# Qwiic_High_Performance_Magnetometer.net
KiCad netlist of a schematic drawn in EAGLE
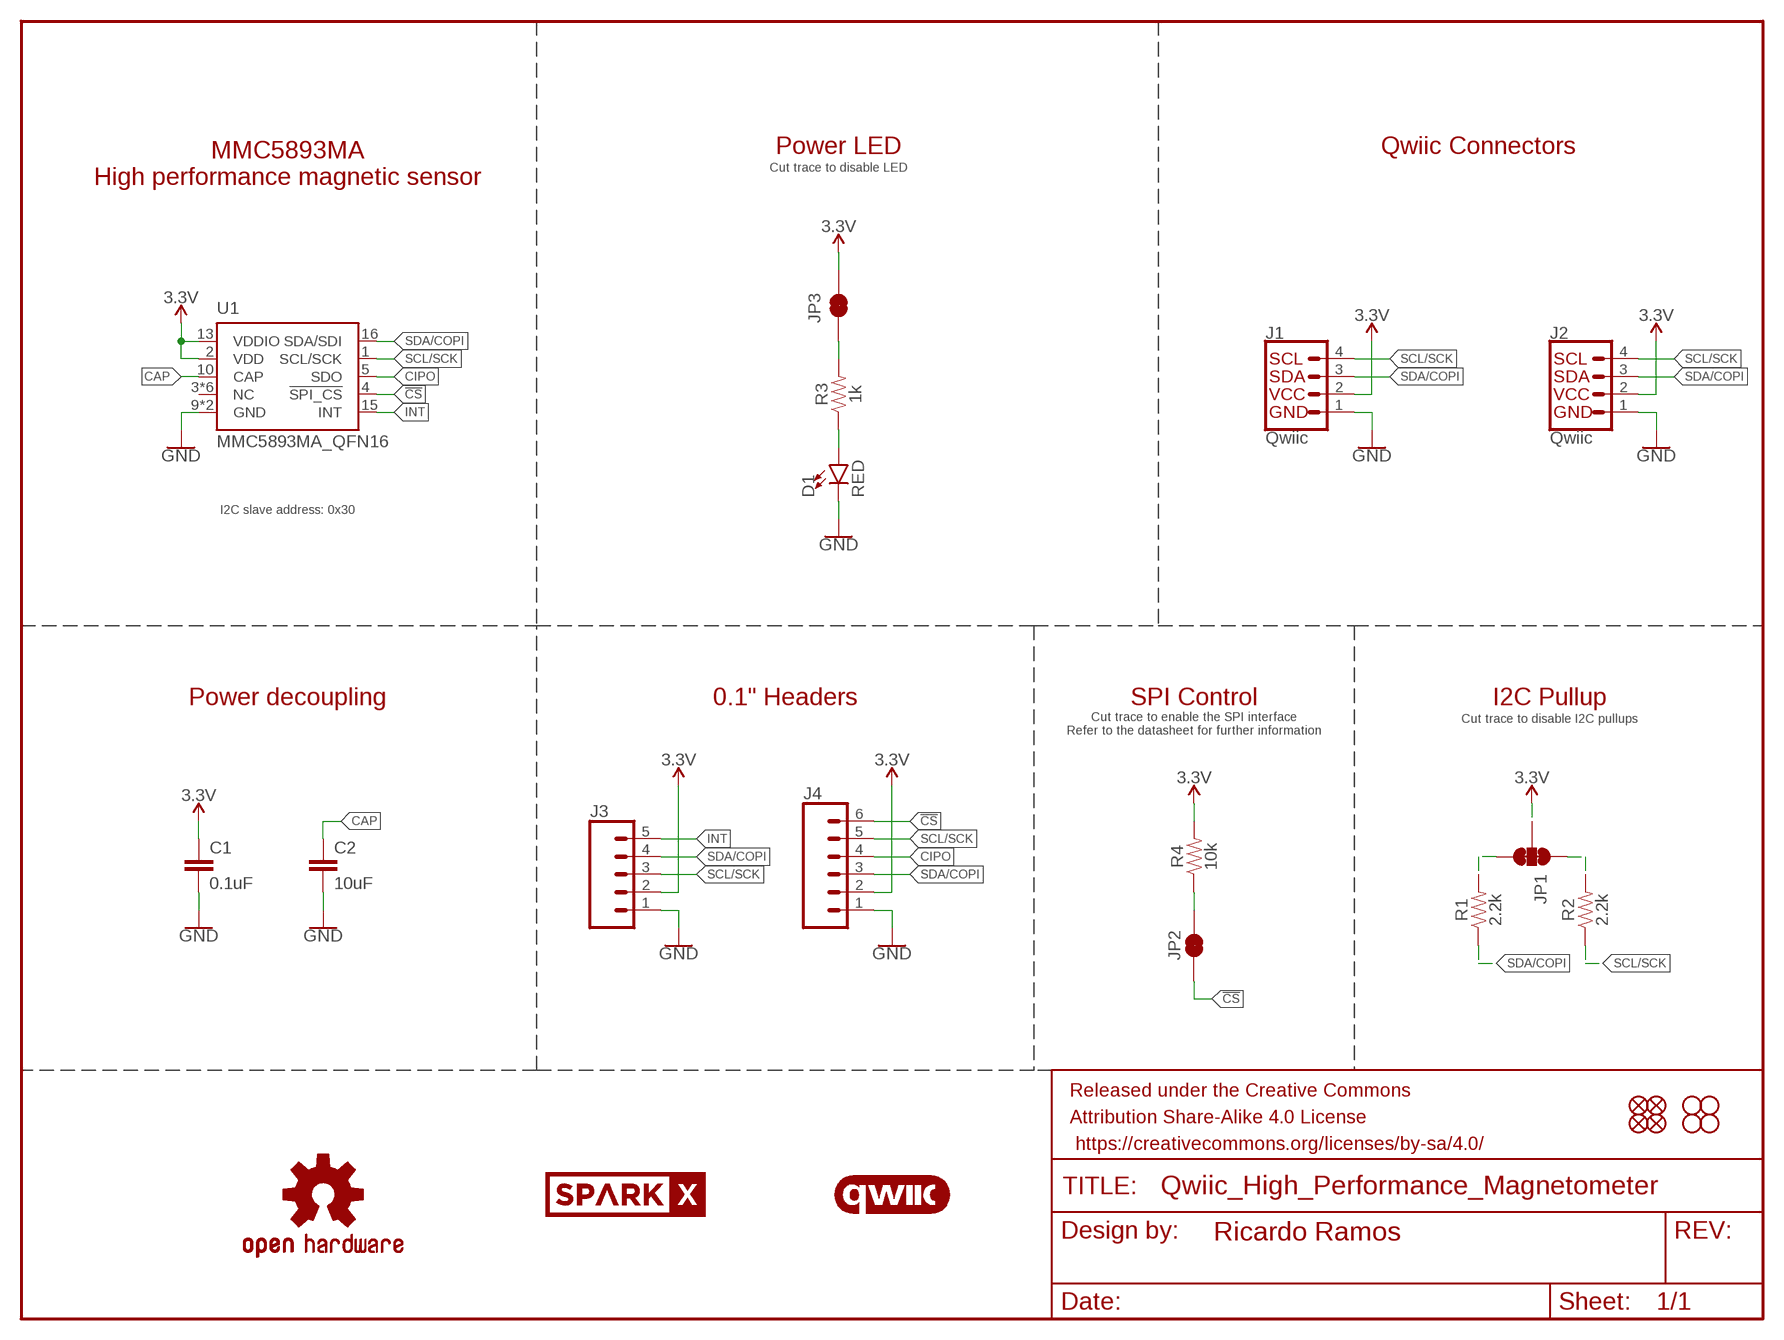
[diagram p0: schematic, sheet 1]

(export (version "E")
  (design (tool "Eeschema 10.0.6"))
  (components
    (comp (ref "C1")
      (value "0.1uF")
      (footprint "eagle-import:0603")
      (libsource (lib "eagle-import") (part "0.1UF-0603-25V-(+80/-20%)"))
    )
    (comp (ref "C2")
      (value "10uF")
      (footprint "eagle-import:0603")
      (libsource (lib "eagle-import") (part "10UF-0603-6.3V-20%"))
    )
    (comp (ref "D1")
      (value "RED")
      (footprint "eagle-import:LED-0603")
      (libsource (lib "eagle-import") (part "LED-RED0603"))
    )
    (comp (ref "FD1")
      (value "FIDUCIAL1X2")
      (footprint "eagle-import:FIDUCIAL-1X2")
      (libsource (lib "eagle-import") (part "FIDUCIAL1X2"))
    )
    (comp (ref "FD2")
      (value "FIDUCIAL1X2")
      (footprint "eagle-import:FIDUCIAL-1X2")
      (libsource (lib "eagle-import") (part "FIDUCIAL1X2"))
    )
    (comp (ref "FD3")
      (value "FIDUCIAL1X2")
      (footprint "eagle-import:FIDUCIAL-1X2")
      (libsource (lib "eagle-import") (part "FIDUCIAL1X2"))
    )
    (comp (ref "FD4")
      (value "FIDUCIAL1X2")
      (footprint "eagle-import:FIDUCIAL-1X2")
      (libsource (lib "eagle-import") (part "FIDUCIAL1X2"))
    )
    (comp (ref "FRAME1")
      (value "FRAME-LETTERNO_PACKAGE")
      (footprint "eagle-import:DUMMY")
      (fields (field (name "DESIGNER") "Nobody") (field (name "DESIGNER_1") "Ricardo Ramos"))
      (libsource (lib "eagle-import") (part "FRAME-LETTERNO_PACKAGE"))
    )
    (comp (ref "H1")
      (value "STAND-OFF")
      (footprint "eagle-import:STAND-OFF")
      (libsource (lib "eagle-import") (part "STAND-OFF"))
    )
    (comp (ref "H2")
      (value "STAND-OFF")
      (footprint "eagle-import:STAND-OFF")
      (libsource (lib "eagle-import") (part "STAND-OFF"))
    )
    (comp (ref "H3")
      (value "STAND-OFF")
      (footprint "eagle-import:STAND-OFF")
      (libsource (lib "eagle-import") (part "STAND-OFF"))
    )
    (comp (ref "H4")
      (value "STAND-OFF")
      (footprint "eagle-import:STAND-OFF")
      (libsource (lib "eagle-import") (part "STAND-OFF"))
    )
    (comp (ref "J1")
      (value "Qwiic")
      (footprint "eagle-import:JST04_1MM_RA")
      (libsource (lib "eagle-import") (part "QWIIC_CONNECTORJS-1MM"))
    )
    (comp (ref "J2")
      (value "Qwiic")
      (footprint "eagle-import:JST04_1MM_RA")
      (libsource (lib "eagle-import") (part "QWIIC_CONNECTORJS-1MM"))
    )
    (comp (ref "J3")
      (value "CONN_05NO_SILK")
      (footprint "eagle-import:1X05_NO_SILK")
      (libsource (lib "eagle-import") (part "CONN_05NO_SILK"))
    )
    (comp (ref "J4")
      (value "CONN_06NO_SILK_NO_POP")
      (footprint "eagle-import:1X06_NO_SILK")
      (libsource (lib "eagle-import") (part "CONN_06NO_SILK_NO_POP"))
    )
    (comp (ref "JP1")
      (value "JUMPER-SMT_3_2-NC_TRACE_SILK")
      (footprint "eagle-import:SMT-JUMPER_3_2-NC_TRACE_SILK")
      (libsource (lib "eagle-import") (part "JUMPER-SMT_3_2-NC_TRACE_SILK"))
    )
    (comp (ref "JP2")
      (value "JUMPER-SMT_2_NC_TRACE_SILK")
      (footprint "eagle-import:SMT-JUMPER_2_NC_TRACE_SILK")
      (libsource (lib "eagle-import") (part "JUMPER-SMT_2_NC_TRACE_SILK"))
    )
    (comp (ref "JP3")
      (value "JUMPER-SMT_2_NC_TRACE_SILK")
      (footprint "eagle-import:SMT-JUMPER_2_NC_TRACE_SILK")
      (libsource (lib "eagle-import") (part "JUMPER-SMT_2_NC_TRACE_SILK"))
    )
    (comp (ref "LOGO1")
      (value "OSHW-LOGOMINI")
      (footprint "eagle-import:OSHW-LOGO-MINI")
      (libsource (lib "eagle-import") (part "OSHW-LOGOMINI"))
    )
    (comp (ref "LOGO2")
      (value "QWIIC_LOGO_5MM")
      (footprint "eagle-import:QWIIC_5MM")
      (libsource (lib "eagle-import") (part "QWIIC_LOGO_5MM"))
    )
    (comp (ref "R1")
      (value "2.2k")
      (footprint "eagle-import:0603")
      (libsource (lib "eagle-import") (part "2.2KOHM-0603-1/10W-1%"))
    )
    (comp (ref "R2")
      (value "2.2k")
      (footprint "eagle-import:0603")
      (libsource (lib "eagle-import") (part "2.2KOHM-0603-1/10W-1%"))
    )
    (comp (ref "R3")
      (value "1k")
      (footprint "eagle-import:0603")
      (libsource (lib "eagle-import") (part "1KOHM-0603-1/10W-1%"))
    )
    (comp (ref "R4")
      (value "10k")
      (footprint "eagle-import:0603")
      (libsource (lib "eagle-import") (part "10KOHM-0603-1/10W-1%"))
    )
    (comp (ref "U$36")
      (value "SPARKX-LOGO2")
      (footprint "eagle-import:SPARKX-TINY")
      (libsource (lib "eagle-import") (part "SPARKX-LOGO2"))
    )
    (comp (ref "U$37")
      (value "SPARKX-LOGO3")
      (footprint "eagle-import:SPARKX-SMALL")
      (libsource (lib "eagle-import") (part "SPARKX-LOGO3"))
    )
    (comp (ref "U1")
      (value "MMC5893MA_QFN16")
      (footprint "eagle-import:LGA-16-3X3MM-4X4PINS")
      (libsource (lib "eagle-import") (part "MMC5893MA_QFN16"))
    )
  )
  (nets
    (net (code "1") (name "/~{CS}") (class "Default")
      (node (ref "J4") (pin "6") (pinfunction "6_6") (pintype "passive"))
      (node (ref "JP2") (pin "1") (pinfunction "1_1") (pintype "passive"))
      (node (ref "U1") (pin "4") (pinfunction "~{SPI_CS}_4") (pintype "input"))
    )
    (net (code "2") (name "3.3V") (class "Default")
      (node (ref "C1") (pin "1") (pinfunction "1_1") (pintype "passive"))
      (node (ref "J1") (pin "2") (pinfunction "2_2") (pintype "power_in"))
      (node (ref "J2") (pin "2") (pinfunction "2_2") (pintype "power_in"))
      (node (ref "J3") (pin "2") (pinfunction "2_2") (pintype "passive"))
      (node (ref "J4") (pin "2") (pinfunction "2_2") (pintype "passive"))
      (node (ref "JP1") (pin "2") (pinfunction "2_2") (pintype "passive"))
      (node (ref "JP3") (pin "2") (pinfunction "2_2") (pintype "passive"))
      (node (ref "R4") (pin "2") (pinfunction "2_2") (pintype "passive"))
      (node (ref "U1") (pin "13") (pinfunction "VDDIO_13") (pintype "power_in"))
      (node (ref "U1") (pin "2") (pinfunction "VDD_2") (pintype "power_in"))
    )
    (net (code "3") (name "CAP") (class "Default")
      (node (ref "C2") (pin "1") (pinfunction "1_1") (pintype "passive"))
      (node (ref "U1") (pin "10") (pinfunction "CAP_10") (pintype "passive"))
    )
    (net (code "4") (name "CIPO") (class "Default")
      (node (ref "J4") (pin "4") (pinfunction "4_4") (pintype "passive"))
      (node (ref "U1") (pin "5") (pinfunction "SDO_5") (pintype "output"))
    )
    (net (code "5") (name "GND") (class "Default")
      (node (ref "C1") (pin "2") (pinfunction "2_2") (pintype "passive"))
      (node (ref "C2") (pin "2") (pinfunction "2_2") (pintype "passive"))
      (node (ref "D1") (pin "C") (pinfunction "C_C") (pintype "passive"))
      (node (ref "J1") (pin "1") (pinfunction "1_1") (pintype "power_in"))
      (node (ref "J2") (pin "1") (pinfunction "1_1") (pintype "power_in"))
      (node (ref "J3") (pin "1") (pinfunction "1_1") (pintype "passive"))
      (node (ref "J4") (pin "1") (pinfunction "1_1") (pintype "passive"))
      (node (ref "U1") (pin "11") (pinfunction "GND_11") (pintype "power_in"))
      (node (ref "U1") (pin "9") (pinfunction "GND_9") (pintype "power_in"))
    )
    (net (code "6") (name "INT") (class "Default")
      (node (ref "J3") (pin "5") (pinfunction "5_5") (pintype "passive"))
      (node (ref "U1") (pin "15") (pinfunction "INT_15") (pintype "output"))
    )
    (net (code "7") (name "Net-(D1-PadA)") (class "Default")
      (node (ref "D1") (pin "A") (pinfunction "A_A") (pintype "passive"))
      (node (ref "R3") (pin "1") (pinfunction "1_1") (pintype "passive"))
    )
    (net (code "8") (name "Net-(JP1-Pad1)") (class "Default")
      (node (ref "JP1") (pin "1") (pinfunction "1_1") (pintype "passive"))
      (node (ref "R2") (pin "2") (pinfunction "2_2") (pintype "passive"))
    )
    (net (code "9") (name "Net-(JP1-Pad3)") (class "Default")
      (node (ref "JP1") (pin "3") (pinfunction "3_3") (pintype "passive"))
      (node (ref "R1") (pin "2") (pinfunction "2_2") (pintype "passive"))
    )
    (net (code "10") (name "Net-(JP2-Pad2)") (class "Default")
      (node (ref "JP2") (pin "2") (pinfunction "2_2") (pintype "passive"))
      (node (ref "R4") (pin "1") (pinfunction "1_1") (pintype "passive"))
    )
    (net (code "11") (name "Net-(JP3-Pad1)") (class "Default")
      (node (ref "JP3") (pin "1") (pinfunction "1_1") (pintype "passive"))
      (node (ref "R3") (pin "2") (pinfunction "2_2") (pintype "passive"))
    )
    (net (code "12") (name "SCL{slash}SCK") (class "Default")
      (node (ref "J1") (pin "4") (pinfunction "4_4") (pintype "passive"))
      (node (ref "J2") (pin "4") (pinfunction "4_4") (pintype "passive"))
      (node (ref "J3") (pin "3") (pinfunction "3_3") (pintype "passive"))
      (node (ref "J4") (pin "5") (pinfunction "5_5") (pintype "passive"))
      (node (ref "R2") (pin "1") (pinfunction "1_1") (pintype "passive"))
      (node (ref "U1") (pin "1") (pinfunction "SCL/SCK_1") (pintype "bidirectional"))
    )
    (net (code "13") (name "SDA{slash}COPI") (class "Default")
      (node (ref "J1") (pin "3") (pinfunction "3_3") (pintype "passive"))
      (node (ref "J2") (pin "3") (pinfunction "3_3") (pintype "passive"))
      (node (ref "J3") (pin "4") (pinfunction "4_4") (pintype "passive"))
      (node (ref "J4") (pin "3") (pinfunction "3_3") (pintype "passive"))
      (node (ref "R1") (pin "1") (pinfunction "1_1") (pintype "passive"))
      (node (ref "U1") (pin "16") (pinfunction "SDA/SDI_16") (pintype "bidirectional"))
    )
    (net (code "14") (name "unconnected-(U1-NC-Pad3)") (class "Default")
      (node (ref "U1") (pin "3") (pinfunction "NC_3") (pintype "no_connect"))
    )
    (net (code "15") (name "unconnected-(U1-NC-Pad6)") (class "Default")
      (node (ref "U1") (pin "6") (pinfunction "NC_6") (pintype "no_connect"))
    )
    (net (code "16") (name "unconnected-(U1-NC-Pad7)") (class "Default")
      (node (ref "U1") (pin "7") (pinfunction "NC_7") (pintype "no_connect"))
    )
    (net (code "17") (name "unconnected-(U1-NC-Pad8)") (class "Default")
      (node (ref "U1") (pin "8") (pinfunction "NC_8") (pintype "no_connect"))
    )
    (net (code "18") (name "unconnected-(U1-NC-Pad12)") (class "Default")
      (node (ref "U1") (pin "12") (pinfunction "NC_12") (pintype "no_connect"))
    )
    (net (code "19") (name "unconnected-(U1-NC-Pad14)") (class "Default")
      (node (ref "U1") (pin "14") (pinfunction "NC_14") (pintype "no_connect"))
    )
  )
)
